# TSOC_GROVEY_GPIO.net
KiCad netlist of a schematic drawn in EAGLE
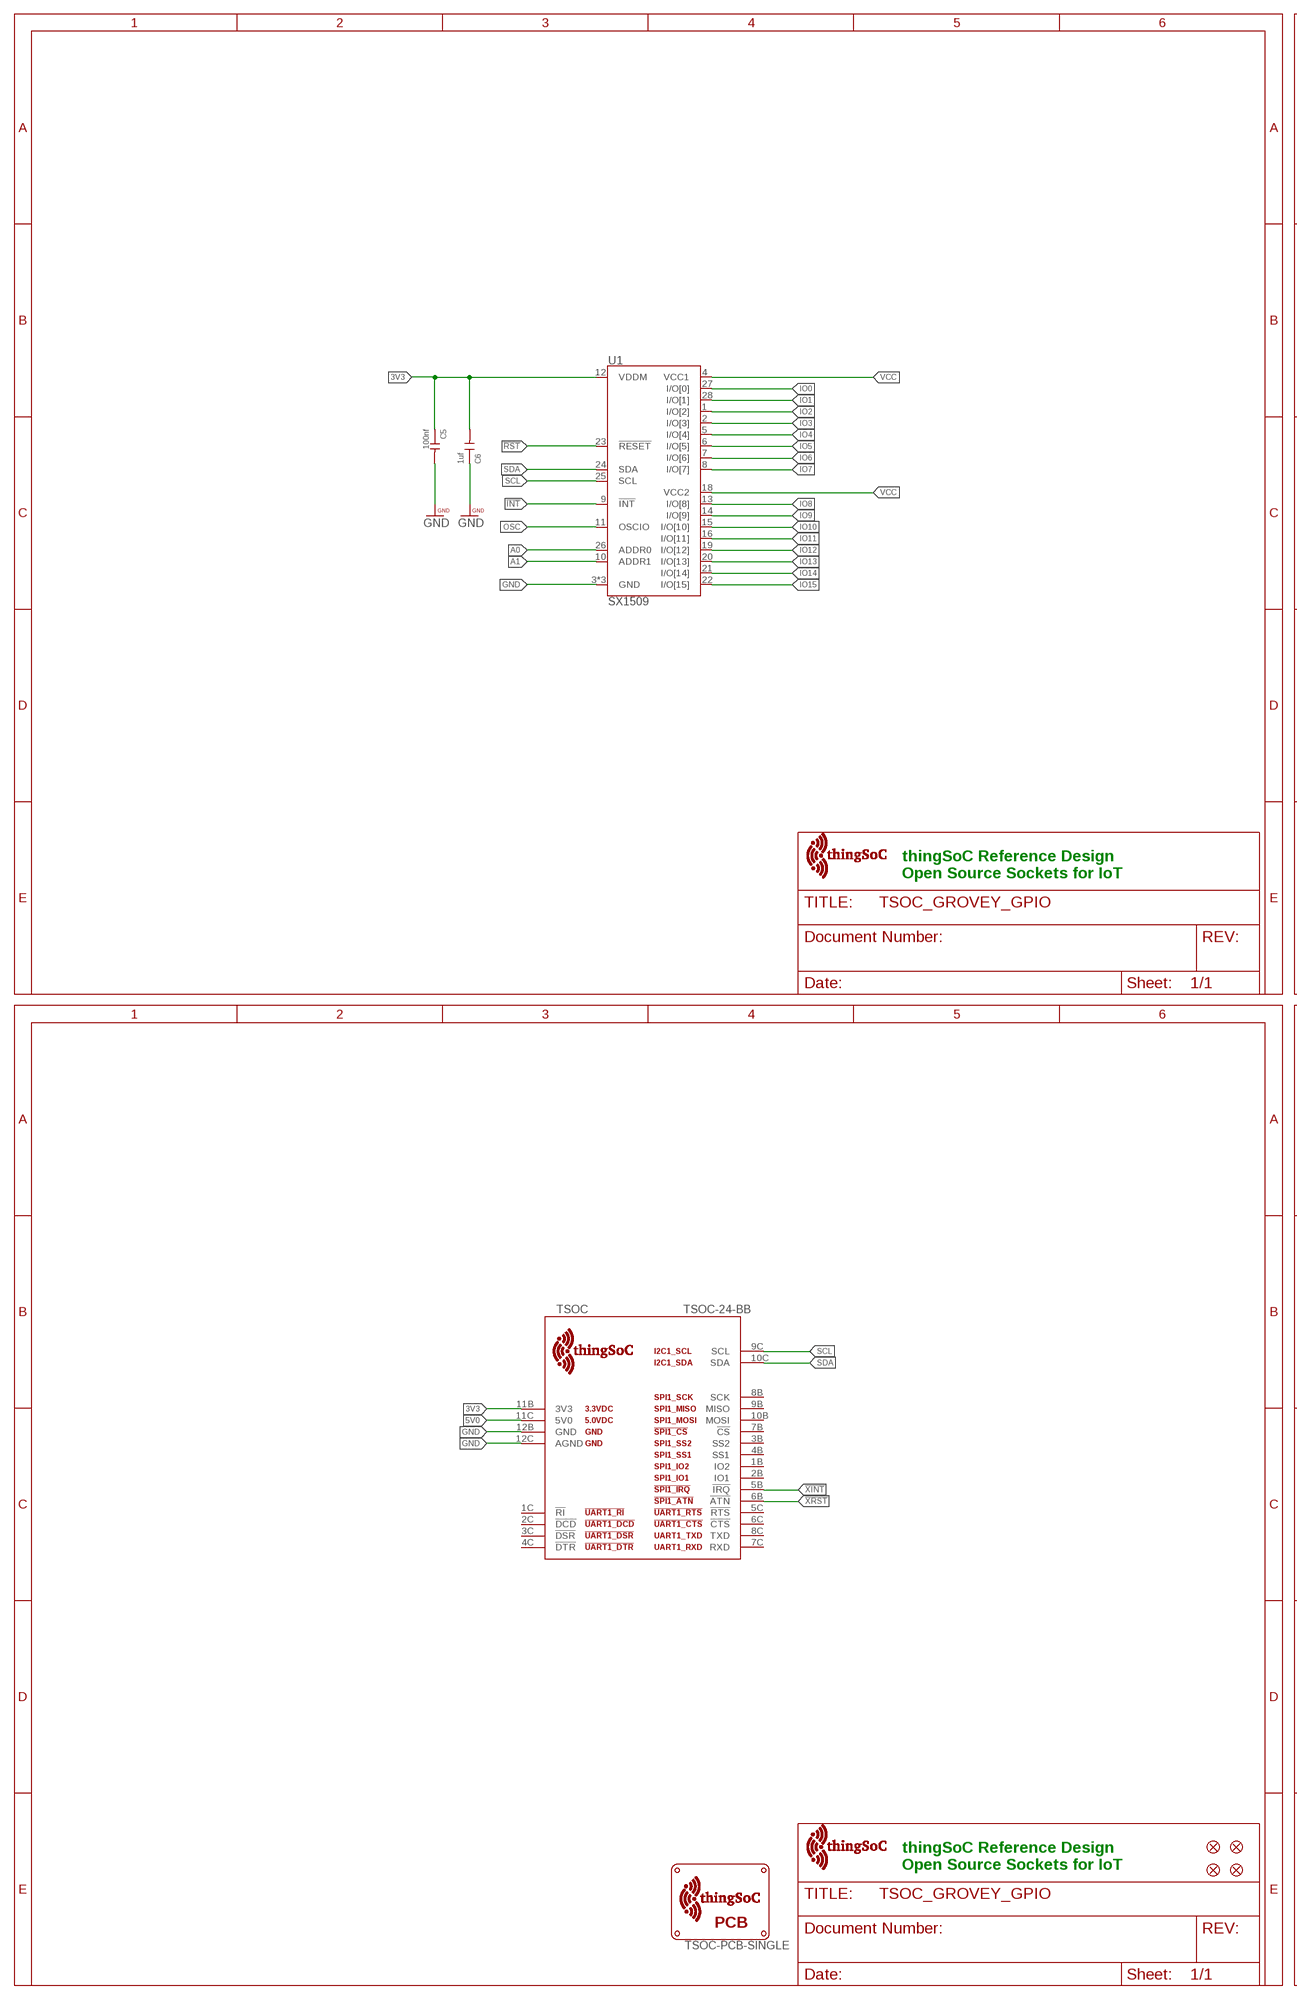
[diagram p0: schematic, sheet 1, part 1 of 2]
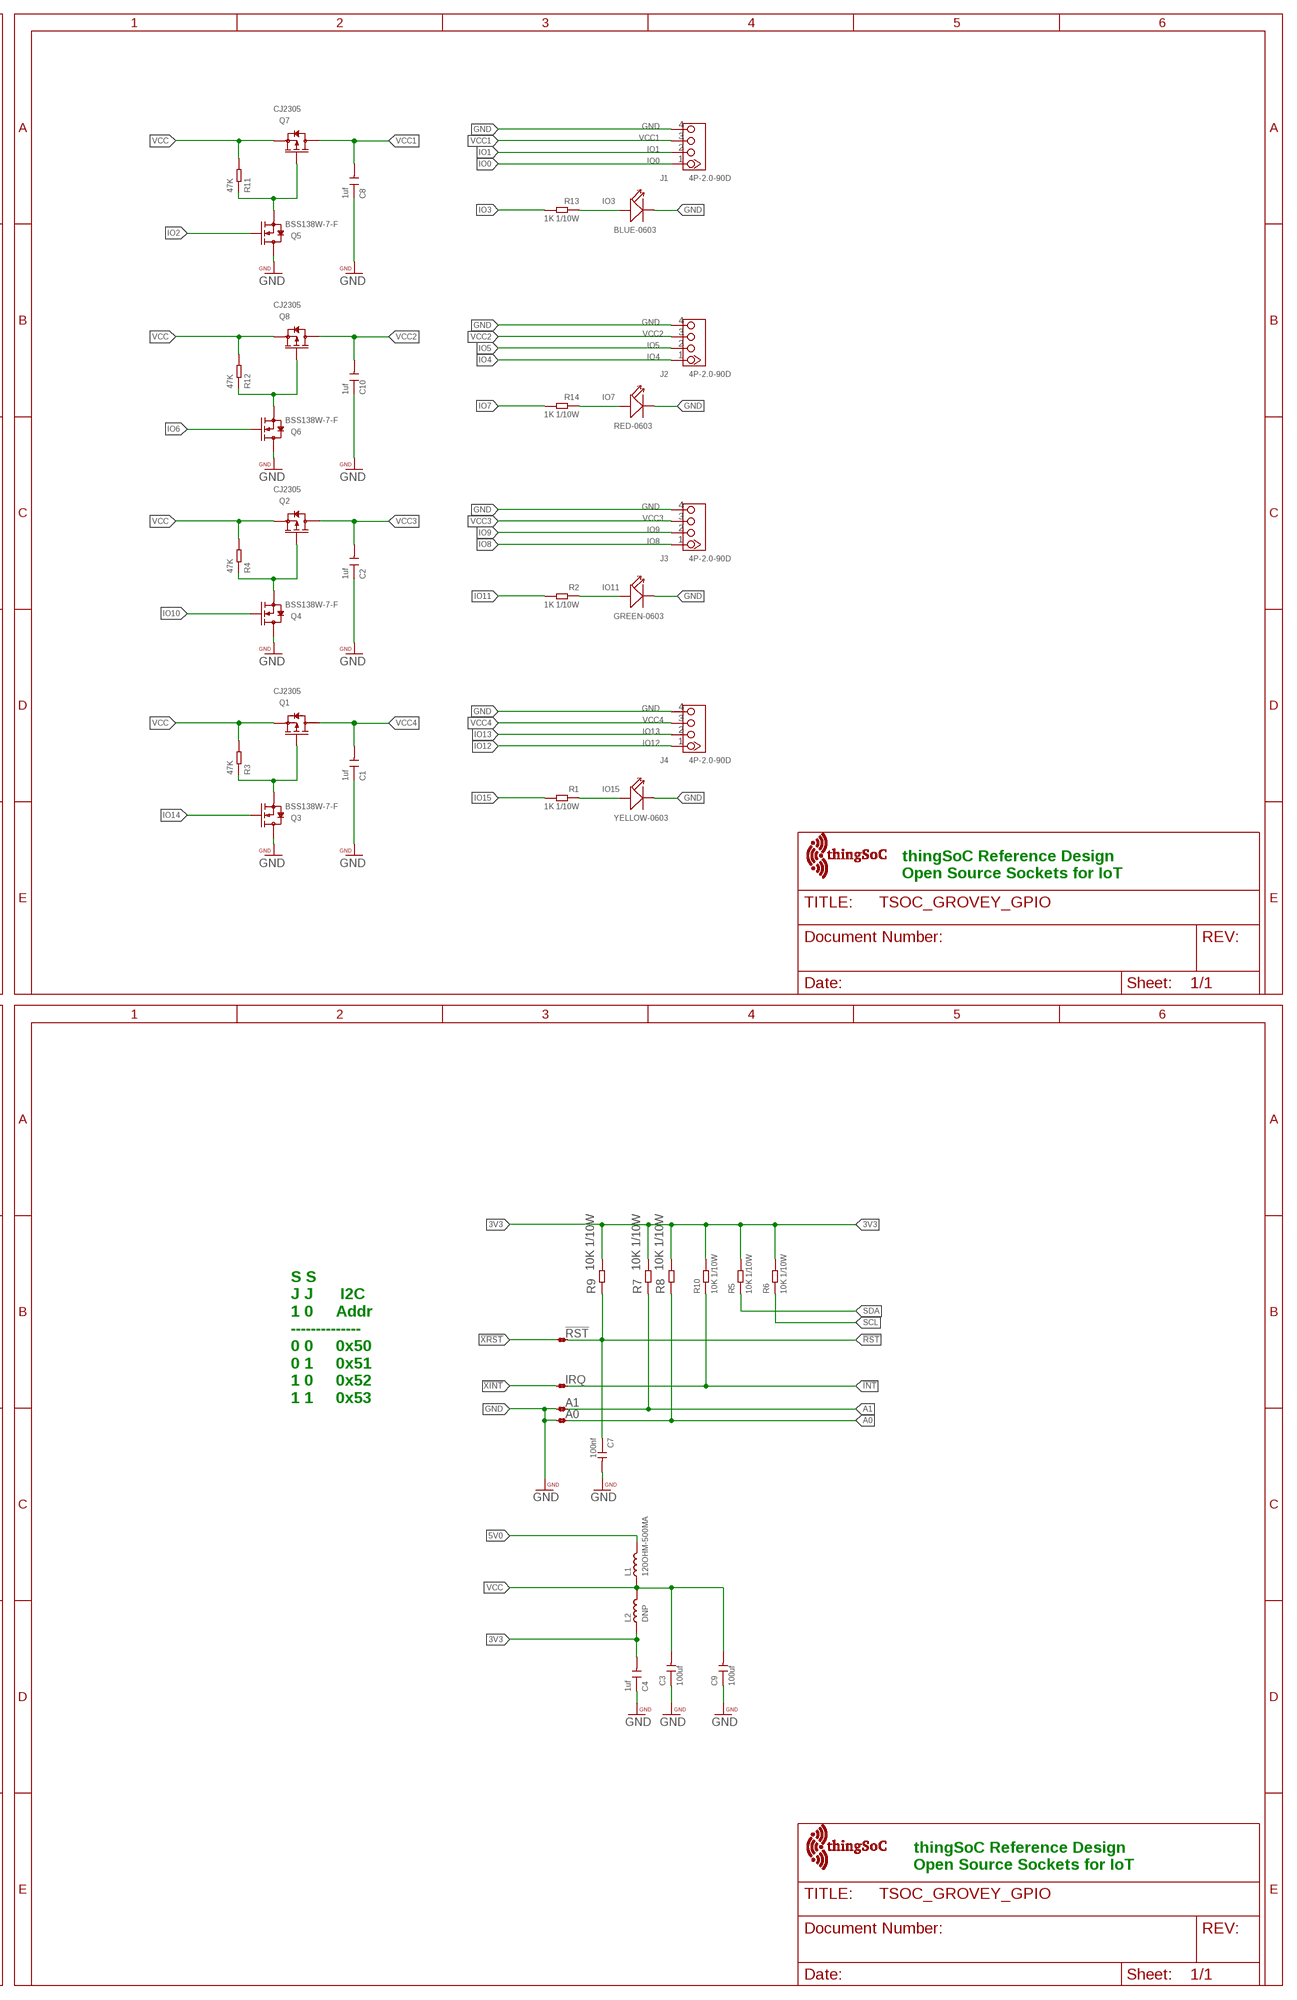
[diagram p1: schematic, sheet 1, part 2 of 2]

(export (version "E")
  (design (tool "Eeschema 10.0.6"))
  (components
    (comp (ref "!RST")
      (value "NO")
      (footprint "eagle-import:JMP-2-NO")
      (libsource (lib "eagle-import") (part "JMP-2-NO"))
    )
    (comp (ref "$$U$4")
      (value "TSOC-LOGO-SMALL")
      (footprint "eagle-import:TSOC-LOGO-SML")
      (libsource (lib "eagle-import") (part "TSOC-LOGO-SMALL"))
    )
    (comp (ref "$$U$5")
      (value "TSOC-LOGO-SMALL")
      (footprint "eagle-import:TSOC-LOGO-SML")
      (libsource (lib "eagle-import") (part "TSOC-LOGO-SMALL"))
    )
    (comp (ref "A0")
      (value "NO")
      (footprint "eagle-import:JMP-2-NO")
      (libsource (lib "eagle-import") (part "JMP-2-NO"))
    )
    (comp (ref "A1")
      (value "NO")
      (footprint "eagle-import:JMP-2-NO")
      (libsource (lib "eagle-import") (part "JMP-2-NO"))
    )
    (comp (ref "C1")
      (value "1uf")
      (footprint "eagle-import:C0603")
      (fields (field (name "MPN") "CC0603KRX7R8BB105"))
      (libsource (lib "eagle-import") (part "CERAMIC-1UF-25V-10%-X7R(0603)"))
    )
    (comp (ref "C2")
      (value "1uf")
      (footprint "eagle-import:C0603")
      (fields (field (name "MPN") "CC0603KRX7R8BB105"))
      (libsource (lib "eagle-import") (part "CERAMIC-1UF-25V-10%-X7R(0603)"))
    )
    (comp (ref "C3")
      (value "100uf")
      (footprint "eagle-import:C1206")
      (fields (field (name "MPN") "GRM31CR60J107ME39L"))
      (libsource (lib "eagle-import") (part "CERAMIC-100UF-6.3V-20%-X5R(1206)"))
    )
    (comp (ref "C4")
      (value "1uf")
      (footprint "eagle-import:C0603")
      (fields (field (name "MPN") "CC0603KRX7R8BB105"))
      (libsource (lib "eagle-import") (part "CERAMIC-1UF-25V-10%-X7R(0603)"))
    )
    (comp (ref "C5")
      (value "100nf")
      (footprint "eagle-import:C0603")
      (fields (field (name "MPN") "CC0603KRX7R9BB104"))
      (libsource (lib "eagle-import") (part "CERAMIC-100NF-50V-10%-X7R(0603)"))
    )
    (comp (ref "C6")
      (value "1uf")
      (footprint "eagle-import:C0603")
      (fields (field (name "MPN") "CC0603KRX7R8BB105"))
      (libsource (lib "eagle-import") (part "CERAMIC-1UF-25V-10%-X7R(0603)"))
    )
    (comp (ref "C7")
      (value "100nf")
      (footprint "eagle-import:C0603")
      (fields (field (name "MPN") "CC0603KRX7R9BB104"))
      (libsource (lib "eagle-import") (part "CERAMIC-100NF-50V-10%-X7R(0603)"))
    )
    (comp (ref "C8")
      (value "1uf")
      (footprint "eagle-import:C0603")
      (fields (field (name "MPN") "CC0603KRX7R8BB105"))
      (libsource (lib "eagle-import") (part "CERAMIC-1UF-25V-10%-X7R(0603)"))
    )
    (comp (ref "C9")
      (value "100uf")
      (footprint "eagle-import:C1206")
      (fields (field (name "MPN") "GRM31CR60J107ME39L"))
      (libsource (lib "eagle-import") (part "CERAMIC-100UF-6.3V-20%-X5R(1206)"))
    )
    (comp (ref "C10")
      (value "1uf")
      (footprint "eagle-import:C0603")
      (fields (field (name "MPN") "CC0603KRX7R8BB105"))
      (libsource (lib "eagle-import") (part "CERAMIC-1UF-25V-10%-X7R(0603)"))
    )
    (comp (ref "FID1")
      (value "FIDUCIALUFIDUCIAL")
      (footprint "eagle-import:MICRO-FIDUCIAL")
      (libsource (lib "eagle-import") (part "FIDUCIALUFIDUCIAL"))
    )
    (comp (ref "FID2")
      (value "FIDUCIALUFIDUCIAL")
      (footprint "eagle-import:MICRO-FIDUCIAL")
      (libsource (lib "eagle-import") (part "FIDUCIALUFIDUCIAL"))
    )
    (comp (ref "FID3")
      (value "FIDUCIALUFIDUCIAL")
      (footprint "eagle-import:MICRO-FIDUCIAL")
      (libsource (lib "eagle-import") (part "FIDUCIALUFIDUCIAL"))
    )
    (comp (ref "FID4")
      (value "FIDUCIALUFIDUCIAL")
      (footprint "eagle-import:MICRO-FIDUCIAL")
      (libsource (lib "eagle-import") (part "FIDUCIALUFIDUCIAL"))
    )
    (comp (ref "IO3")
      (value "BLUE-0603")
      (footprint "eagle-import:LED-0603")
      (fields (field (name "MPN") "19-217-BHC-ZL1M2RY-3T"))
      (libsource (lib "eagle-import") (part "SMD-LED-CLEAR-BLUE(0603)"))
    )
    (comp (ref "IO7")
      (value "RED-0603")
      (footprint "eagle-import:LED-0603")
      (fields (field (name "MPN") "19-217-R6C-AL1M2VY-3T"))
      (libsource (lib "eagle-import") (part "LED-SMD-RED-DIFFUSED(0603)"))
    )
    (comp (ref "IO11")
      (value "GREEN-0603")
      (footprint "eagle-import:LED-0603")
      (fields (field (name "MPN") "19-217-G7C-AN1P2-3T"))
      (libsource (lib "eagle-import") (part "SMD-LED-CLEAR-GREEN(0603)"))
    )
    (comp (ref "IO15")
      (value "YELLOW-0603")
      (footprint "eagle-import:LED-0603")
      (fields (field (name "MPN") "19-217-Y5C-AM1N1VY-3T"))
      (libsource (lib "eagle-import") (part "SMD-LED-CLEAR-YELLOW(0603)"))
    )
    (comp (ref "IRQ")
      (value "NO")
      (footprint "eagle-import:JMP-2-NO")
      (libsource (lib "eagle-import") (part "JMP-2-NO"))
    )
    (comp (ref "J1")
      (value "4P-2.0-90D")
      (footprint "eagle-import:HW4-2.0-90D")
      (libsource (lib "eagle-import") (part "GROVE-CONNECTOR-DIP-90D(4P-2.0)"))
    )
    (comp (ref "J2")
      (value "4P-2.0-90D")
      (footprint "eagle-import:HW4-2.0-90D")
      (libsource (lib "eagle-import") (part "GROVE-CONNECTOR-DIP-90D(4P-2.0)"))
    )
    (comp (ref "J3")
      (value "4P-2.0-90D")
      (footprint "eagle-import:HW4-2.0-90D")
      (libsource (lib "eagle-import") (part "GROVE-CONNECTOR-DIP-90D(4P-2.0)"))
    )
    (comp (ref "J4")
      (value "4P-2.0-90D")
      (footprint "eagle-import:HW4-2.0-90D")
      (libsource (lib "eagle-import") (part "GROVE-CONNECTOR-DIP-90D(4P-2.0)"))
    )
    (comp (ref "L1")
      (value "120OHM-500MA")
      (footprint "eagle-import:L0603")
      (fields (field (name "MPN") "BLM18AG121SN1D"))
      (libsource (lib "eagle-import") (part "SMD-FERRITE-CHIP-120-OHM-500MA(0603)"))
    )
    (comp (ref "L2")
      (value "DNP")
      (footprint "eagle-import:L0603")
      (fields (field (name "MPN") "BLM18AG121SN1D"))
      (libsource (lib "eagle-import") (part "SMD-FERRITE-CHIP-120-OHM-500MA(0603)"))
    )
    (comp (ref "Q1")
      (value "CJ2305")
      (footprint "eagle-import:SOT-23")
      (libsource (lib "eagle-import") (part "SMD-MOSFET-P-CH-8V-4.1A-CJ2305(SOT-23)"))
    )
    (comp (ref "Q2")
      (value "CJ2305")
      (footprint "eagle-import:SOT-23")
      (libsource (lib "eagle-import") (part "SMD-MOSFET-P-CH-8V-4.1A-CJ2305(SOT-23)"))
    )
    (comp (ref "Q3")
      (value "BSS138W-7-F")
      (footprint "eagle-import:SOT-23")
      (libsource (lib "eagle-import") (part "SMD-MOSFET-N-CH-50V-200MA-BSS138W-7-F(SOT-23)"))
    )
    (comp (ref "Q4")
      (value "BSS138W-7-F")
      (footprint "eagle-import:SOT-23")
      (libsource (lib "eagle-import") (part "SMD-MOSFET-N-CH-50V-200MA-BSS138W-7-F(SOT-23)"))
    )
    (comp (ref "Q5")
      (value "BSS138W-7-F")
      (footprint "eagle-import:SOT-23")
      (libsource (lib "eagle-import") (part "SMD-MOSFET-N-CH-50V-200MA-BSS138W-7-F(SOT-23)"))
    )
    (comp (ref "Q6")
      (value "BSS138W-7-F")
      (footprint "eagle-import:SOT-23")
      (libsource (lib "eagle-import") (part "SMD-MOSFET-N-CH-50V-200MA-BSS138W-7-F(SOT-23)"))
    )
    (comp (ref "Q7")
      (value "CJ2305")
      (footprint "eagle-import:SOT-23")
      (libsource (lib "eagle-import") (part "SMD-MOSFET-P-CH-8V-4.1A-CJ2305(SOT-23)"))
    )
    (comp (ref "Q8")
      (value "CJ2305")
      (footprint "eagle-import:SOT-23")
      (libsource (lib "eagle-import") (part "SMD-MOSFET-P-CH-8V-4.1A-CJ2305(SOT-23)"))
    )
    (comp (ref "R1")
      (value "1K 1/10W")
      (footprint "eagle-import:R0603")
      (fields (field (name "MPN") "RC0603JR-071KL"))
      (libsource (lib "eagle-import") (part "SMD-RES-1K-5%-1/10W(0603)"))
    )
    (comp (ref "R2")
      (value "1K 1/10W")
      (footprint "eagle-import:R0603")
      (fields (field (name "MPN") "RC0603JR-071KL"))
      (libsource (lib "eagle-import") (part "SMD-RES-1K-5%-1/10W(0603)"))
    )
    (comp (ref "R3")
      (value "47K")
      (footprint "eagle-import:R0603")
      (fields (field (name "MPN") "RC0603JR-0747KL"))
      (libsource (lib "eagle-import") (part "SMD-RES-47K-5%-1/10W(0603)"))
    )
    (comp (ref "R4")
      (value "47K")
      (footprint "eagle-import:R0603")
      (fields (field (name "MPN") "RC0603JR-0747KL"))
      (libsource (lib "eagle-import") (part "SMD-RES-47K-5%-1/10W(0603)"))
    )
    (comp (ref "R5")
      (value "10K 1/10W")
      (footprint "eagle-import:R0603")
      (fields (field (name "MPN") "RC0603JR-0710KL"))
      (libsource (lib "eagle-import") (part "SMD-RES-10K-5%-1/10W(0603)"))
    )
    (comp (ref "R6")
      (value "10K 1/10W")
      (footprint "eagle-import:R0603")
      (fields (field (name "MPN") "RC0603JR-0710KL"))
      (libsource (lib "eagle-import") (part "SMD-RES-10K-5%-1/10W(0603)"))
    )
    (comp (ref "R7")
      (value "10K 1/10W")
      (footprint "eagle-import:R0603")
      (fields (field (name "MPN") "RC0603JR-0710KL"))
      (libsource (lib "eagle-import") (part "SMD-RES-10K-5%-1/10W(0603)"))
    )
    (comp (ref "R8")
      (value "10K 1/10W")
      (footprint "eagle-import:R0603")
      (fields (field (name "MPN") "RC0603JR-0710KL"))
      (libsource (lib "eagle-import") (part "SMD-RES-10K-5%-1/10W(0603)"))
    )
    (comp (ref "R9")
      (value "10K 1/10W")
      (footprint "eagle-import:R0603")
      (fields (field (name "MPN") "RC0603JR-0710KL"))
      (libsource (lib "eagle-import") (part "SMD-RES-10K-5%-1/10W(0603)"))
    )
    (comp (ref "R10")
      (value "10K 1/10W")
      (footprint "eagle-import:R0603")
      (fields (field (name "MPN") "RC0603JR-0710KL"))
      (libsource (lib "eagle-import") (part "SMD-RES-10K-5%-1/10W(0603)"))
    )
    (comp (ref "R11")
      (value "47K")
      (footprint "eagle-import:R0603")
      (fields (field (name "MPN") "RC0603JR-0747KL"))
      (libsource (lib "eagle-import") (part "SMD-RES-47K-5%-1/10W(0603)"))
    )
    (comp (ref "R12")
      (value "47K")
      (footprint "eagle-import:R0603")
      (fields (field (name "MPN") "RC0603JR-0747KL"))
      (libsource (lib "eagle-import") (part "SMD-RES-47K-5%-1/10W(0603)"))
    )
    (comp (ref "R13")
      (value "1K 1/10W")
      (footprint "eagle-import:R0603")
      (fields (field (name "MPN") "RC0603JR-071KL"))
      (libsource (lib "eagle-import") (part "SMD-RES-1K-5%-1/10W(0603)"))
    )
    (comp (ref "R14")
      (value "1K 1/10W")
      (footprint "eagle-import:R0603")
      (fields (field (name "MPN") "RC0603JR-071KL"))
      (libsource (lib "eagle-import") (part "SMD-RES-1K-5%-1/10W(0603)"))
    )
    (comp (ref "TSOC")
      (value "TSOC-24-BB")
      (footprint "eagle-import:TSOC-BB-S24")
      (libsource (lib "eagle-import") (part "TSOC-24-BB"))
    )
    (comp (ref "U$3")
      (value "TSOC-PCB-SINGLE")
      (footprint "eagle-import:TSOC-BB-BRD-DIM")
      (libsource (lib "eagle-import") (part "TSOC-PCB-SINGLE"))
    )
    (comp (ref "U$101")
      (value "TSOC-LOGO-LRG")
      (footprint "eagle-import:TSOC-LOGO-LRG")
      (libsource (lib "eagle-import") (part "TSOC-LOGO-LRG"))
    )
    (comp (ref "U$102")
      (value "TSOC-LOGO-SMALL")
      (footprint "eagle-import:TSOC-LOGO-SML")
      (libsource (lib "eagle-import") (part "TSOC-LOGO-SMALL"))
    )
    (comp (ref "U1")
      (value "SX1509")
      (footprint "eagle-import:QFN-28")
      (libsource (lib "eagle-import") (part "SX1509"))
    )
  )
  (nets
    (net (code "1") (name "/~{INT}") (class "Default")
      (node (ref "IRQ") (pin "2") (pinfunction "2_2") (pintype "passive"))
      (node (ref "R10") (pin "1") (pinfunction "1_1") (pintype "passive"))
      (node (ref "U1") (pin "9") (pinfunction "~{INT}_9") (pintype "bidirectional"))
    )
    (net (code "2") (name "/~{RST}") (class "Default")
      (node (ref "!RST") (pin "1") (pinfunction "1_1") (pintype "passive"))
      (node (ref "C7") (pin "1") (pinfunction "1_1") (pintype "passive"))
      (node (ref "R9") (pin "1") (pinfunction "1_1") (pintype "passive"))
      (node (ref "U1") (pin "23") (pinfunction "~{RESET}_23") (pintype "bidirectional"))
    )
    (net (code "3") (name "/~{XINT}") (class "Default")
      (node (ref "IRQ") (pin "1") (pinfunction "1_1") (pintype "passive"))
      (node (ref "TSOC") (pin "5B") (pinfunction "~{IRQ}_5B") (pintype "bidirectional"))
    )
    (net (code "4") (name "/~{XRST}") (class "Default")
      (node (ref "!RST") (pin "2") (pinfunction "2_2") (pintype "passive"))
      (node (ref "TSOC") (pin "6B") (pinfunction "~{ATN}_6B") (pintype "bidirectional"))
    )
    (net (code "5") (name "3V3") (class "Default")
      (node (ref "C4") (pin "2") (pinfunction "2_2") (pintype "passive"))
      (node (ref "C5") (pin "1") (pinfunction "1_1") (pintype "passive"))
      (node (ref "C6") (pin "2") (pinfunction "2_2") (pintype "passive"))
      (node (ref "L2") (pin "1") (pinfunction "1_1") (pintype "passive"))
      (node (ref "R10") (pin "2") (pinfunction "2_2") (pintype "passive"))
      (node (ref "R5") (pin "2") (pinfunction "2_2") (pintype "passive"))
      (node (ref "R6") (pin "2") (pinfunction "2_2") (pintype "passive"))
      (node (ref "R7") (pin "2") (pinfunction "2_2") (pintype "passive"))
      (node (ref "R8") (pin "2") (pinfunction "2_2") (pintype "passive"))
      (node (ref "R9") (pin "2") (pinfunction "2_2") (pintype "passive"))
      (node (ref "TSOC") (pin "11B") (pinfunction "3V3_11B") (pintype "bidirectional"))
      (node (ref "U1") (pin "12") (pinfunction "VDDM_12") (pintype "bidirectional"))
    )
    (net (code "6") (name "5V0") (class "Default")
      (node (ref "L1") (pin "2") (pinfunction "2_2") (pintype "passive"))
      (node (ref "TSOC") (pin "11C") (pinfunction "5V0_11C") (pintype "bidirectional"))
    )
    (net (code "7") (name "A0") (class "Default")
      (node (ref "A0") (pin "2") (pinfunction "2_2") (pintype "passive"))
      (node (ref "R8") (pin "1") (pinfunction "1_1") (pintype "passive"))
      (node (ref "U1") (pin "26") (pinfunction "ADDR0_26") (pintype "bidirectional"))
    )
    (net (code "8") (name "A1") (class "Default")
      (node (ref "A1") (pin "2") (pinfunction "2_2") (pintype "passive"))
      (node (ref "R7") (pin "1") (pinfunction "1_1") (pintype "passive"))
      (node (ref "U1") (pin "10") (pinfunction "ADDR1_10") (pintype "bidirectional"))
    )
    (net (code "9") (name "GND") (class "Default")
      (node (ref "A0") (pin "1") (pinfunction "1_1") (pintype "passive"))
      (node (ref "A1") (pin "1") (pinfunction "1_1") (pintype "passive"))
      (node (ref "C1") (pin "1") (pinfunction "1_1") (pintype "passive"))
      (node (ref "C10") (pin "1") (pinfunction "1_1") (pintype "passive"))
      (node (ref "C2") (pin "1") (pinfunction "1_1") (pintype "passive"))
      (node (ref "C3") (pin "1") (pinfunction "1_1") (pintype "passive"))
      (node (ref "C4") (pin "1") (pinfunction "1_1") (pintype "passive"))
      (node (ref "C5") (pin "2") (pinfunction "2_2") (pintype "passive"))
      (node (ref "C6") (pin "1") (pinfunction "1_1") (pintype "passive"))
      (node (ref "C7") (pin "2") (pinfunction "2_2") (pintype "passive"))
      (node (ref "C8") (pin "1") (pinfunction "1_1") (pintype "passive"))
      (node (ref "C9") (pin "1") (pinfunction "1_1") (pintype "passive"))
      (node (ref "IO11") (pin "-") (pinfunction "-_-") (pintype "passive"))
      (node (ref "IO15") (pin "-") (pinfunction "-_-") (pintype "passive"))
      (node (ref "IO3") (pin "-") (pinfunction "-_-") (pintype "passive"))
      (node (ref "IO7") (pin "-") (pinfunction "-_-") (pintype "passive"))
      (node (ref "J1") (pin "4") (pinfunction "4_4") (pintype "bidirectional"))
      (node (ref "J2") (pin "4") (pinfunction "4_4") (pintype "bidirectional"))
      (node (ref "J3") (pin "4") (pinfunction "4_4") (pintype "bidirectional"))
      (node (ref "J4") (pin "4") (pinfunction "4_4") (pintype "bidirectional"))
      (node (ref "Q3") (pin "3") (pinfunction "D_3") (pintype "passive"))
      (node (ref "Q4") (pin "3") (pinfunction "D_3") (pintype "passive"))
      (node (ref "Q5") (pin "3") (pinfunction "D_3") (pintype "passive"))
      (node (ref "Q6") (pin "3") (pinfunction "D_3") (pintype "passive"))
      (node (ref "TSOC") (pin "12B") (pinfunction "GND_12B") (pintype "bidirectional"))
      (node (ref "TSOC") (pin "12C") (pinfunction "AGND_12C") (pintype "bidirectional"))
      (node (ref "U1") (pin "17") (pinfunction "GND_17") (pintype "bidirectional"))
      (node (ref "U1") (pin "29") (pinfunction "GND_29") (pintype "bidirectional"))
      (node (ref "U1") (pin "3") (pinfunction "GND_3") (pintype "bidirectional"))
    )
    (net (code "10") (name "IO0") (class "Default")
      (node (ref "J1") (pin "1") (pinfunction "1_1") (pintype "bidirectional"))
      (node (ref "U1") (pin "27") (pinfunction "I/O[0]_27") (pintype "bidirectional"))
    )
    (net (code "11") (name "IO1") (class "Default")
      (node (ref "J1") (pin "2") (pinfunction "2_2") (pintype "bidirectional"))
      (node (ref "U1") (pin "28") (pinfunction "I/O[1]_28") (pintype "bidirectional"))
    )
    (net (code "12") (name "IO2") (class "Default")
      (node (ref "Q5") (pin "1") (pinfunction "G_1") (pintype "passive"))
      (node (ref "U1") (pin "1") (pinfunction "I/O[2]_1") (pintype "bidirectional"))
    )
    (net (code "13") (name "IO3") (class "Default")
      (node (ref "R13") (pin "2") (pinfunction "2_2") (pintype "passive"))
      (node (ref "U1") (pin "2") (pinfunction "I/O[3]_2") (pintype "bidirectional"))
    )
    (net (code "14") (name "IO4") (class "Default")
      (node (ref "J2") (pin "1") (pinfunction "1_1") (pintype "bidirectional"))
      (node (ref "U1") (pin "5") (pinfunction "I/O[4]_5") (pintype "bidirectional"))
    )
    (net (code "15") (name "IO5") (class "Default")
      (node (ref "J2") (pin "2") (pinfunction "2_2") (pintype "bidirectional"))
      (node (ref "U1") (pin "6") (pinfunction "I/O[5]_6") (pintype "bidirectional"))
    )
    (net (code "16") (name "IO6") (class "Default")
      (node (ref "Q6") (pin "1") (pinfunction "G_1") (pintype "passive"))
      (node (ref "U1") (pin "7") (pinfunction "I/O[6]_7") (pintype "bidirectional"))
    )
    (net (code "17") (name "IO7") (class "Default")
      (node (ref "R14") (pin "2") (pinfunction "2_2") (pintype "passive"))
      (node (ref "U1") (pin "8") (pinfunction "I/O[7]_8") (pintype "bidirectional"))
    )
    (net (code "18") (name "IO8") (class "Default")
      (node (ref "J3") (pin "1") (pinfunction "1_1") (pintype "bidirectional"))
      (node (ref "U1") (pin "13") (pinfunction "I/O[8]_13") (pintype "bidirectional"))
    )
    (net (code "19") (name "IO9") (class "Default")
      (node (ref "J3") (pin "2") (pinfunction "2_2") (pintype "bidirectional"))
      (node (ref "U1") (pin "14") (pinfunction "I/O[9]_14") (pintype "bidirectional"))
    )
    (net (code "20") (name "IO10") (class "Default")
      (node (ref "Q4") (pin "1") (pinfunction "G_1") (pintype "passive"))
      (node (ref "U1") (pin "15") (pinfunction "I/O[10]_15") (pintype "bidirectional"))
    )
    (net (code "21") (name "IO11") (class "Default")
      (node (ref "R2") (pin "2") (pinfunction "2_2") (pintype "passive"))
      (node (ref "U1") (pin "16") (pinfunction "I/O[11]_16") (pintype "bidirectional"))
    )
    (net (code "22") (name "IO12") (class "Default")
      (node (ref "J4") (pin "1") (pinfunction "1_1") (pintype "bidirectional"))
      (node (ref "U1") (pin "19") (pinfunction "I/O[12]_19") (pintype "bidirectional"))
    )
    (net (code "23") (name "IO13") (class "Default")
      (node (ref "J4") (pin "2") (pinfunction "2_2") (pintype "bidirectional"))
      (node (ref "U1") (pin "20") (pinfunction "I/O[13]_20") (pintype "bidirectional"))
    )
    (net (code "24") (name "IO14") (class "Default")
      (node (ref "Q3") (pin "1") (pinfunction "G_1") (pintype "passive"))
      (node (ref "U1") (pin "21") (pinfunction "I/O[14]_21") (pintype "bidirectional"))
    )
    (net (code "25") (name "IO15") (class "Default")
      (node (ref "R1") (pin "2") (pinfunction "2_2") (pintype "passive"))
      (node (ref "U1") (pin "22") (pinfunction "I/O[15]_22") (pintype "bidirectional"))
    )
    (net (code "26") (name "Net-(IO3-Pad+)") (class "Default")
      (node (ref "IO3") (pin "+") (pinfunction "+_+") (pintype "passive"))
      (node (ref "R13") (pin "1") (pinfunction "1_1") (pintype "passive"))
    )
    (net (code "27") (name "Net-(IO7-Pad+)") (class "Default")
      (node (ref "IO7") (pin "+") (pinfunction "+_+") (pintype "passive"))
      (node (ref "R14") (pin "1") (pinfunction "1_1") (pintype "passive"))
    )
    (net (code "28") (name "Net-(IO11-Pad+)") (class "Default")
      (node (ref "IO11") (pin "+") (pinfunction "+_+") (pintype "passive"))
      (node (ref "R2") (pin "1") (pinfunction "1_1") (pintype "passive"))
    )
    (net (code "29") (name "Net-(IO15-Pad+)") (class "Default")
      (node (ref "IO15") (pin "+") (pinfunction "+_+") (pintype "passive"))
      (node (ref "R1") (pin "1") (pinfunction "1_1") (pintype "passive"))
    )
    (net (code "30") (name "Net-(Q1-G)") (class "Default")
      (node (ref "Q1") (pin "1") (pinfunction "G_1") (pintype "passive"))
      (node (ref "Q3") (pin "2") (pinfunction "S_2") (pintype "passive"))
      (node (ref "R3") (pin "1") (pinfunction "1_1") (pintype "passive"))
    )
    (net (code "31") (name "Net-(Q2-G)") (class "Default")
      (node (ref "Q2") (pin "1") (pinfunction "G_1") (pintype "passive"))
      (node (ref "Q4") (pin "2") (pinfunction "S_2") (pintype "passive"))
      (node (ref "R4") (pin "1") (pinfunction "1_1") (pintype "passive"))
    )
    (net (code "32") (name "Net-(Q5-S)") (class "Default")
      (node (ref "Q5") (pin "2") (pinfunction "S_2") (pintype "passive"))
      (node (ref "Q7") (pin "1") (pinfunction "G_1") (pintype "passive"))
      (node (ref "R11") (pin "1") (pinfunction "1_1") (pintype "passive"))
    )
    (net (code "33") (name "Net-(Q6-S)") (class "Default")
      (node (ref "Q6") (pin "2") (pinfunction "S_2") (pintype "passive"))
      (node (ref "Q8") (pin "1") (pinfunction "G_1") (pintype "passive"))
      (node (ref "R12") (pin "1") (pinfunction "1_1") (pintype "passive"))
    )
    (net (code "34") (name "OSC") (class "Default")
      (node (ref "U1") (pin "11") (pinfunction "OSCIO_11") (pintype "bidirectional"))
    )
    (net (code "35") (name "SCL") (class "Default")
      (node (ref "R6") (pin "1") (pinfunction "1_1") (pintype "passive"))
      (node (ref "TSOC") (pin "9C") (pinfunction "SCL_9C") (pintype "bidirectional"))
      (node (ref "U1") (pin "25") (pinfunction "SCL_25") (pintype "bidirectional"))
    )
    (net (code "36") (name "SDA") (class "Default")
      (node (ref "R5") (pin "1") (pinfunction "1_1") (pintype "passive"))
      (node (ref "TSOC") (pin "10C") (pinfunction "SDA_10C") (pintype "bidirectional"))
      (node (ref "U1") (pin "24") (pinfunction "SDA_24") (pintype "bidirectional"))
    )
    (net (code "37") (name "VCC") (class "Default")
      (node (ref "C3") (pin "2") (pinfunction "2_2") (pintype "passive"))
      (node (ref "C9") (pin "2") (pinfunction "2_2") (pintype "passive"))
      (node (ref "L1") (pin "1") (pinfunction "1_1") (pintype "passive"))
      (node (ref "L2") (pin "2") (pinfunction "2_2") (pintype "passive"))
      (node (ref "Q1") (pin "2") (pinfunction "S_2") (pintype "passive"))
      (node (ref "Q2") (pin "2") (pinfunction "S_2") (pintype "passive"))
      (node (ref "Q7") (pin "2") (pinfunction "S_2") (pintype "passive"))
      (node (ref "Q8") (pin "2") (pinfunction "S_2") (pintype "passive"))
      (node (ref "R11") (pin "2") (pinfunction "2_2") (pintype "passive"))
      (node (ref "R12") (pin "2") (pinfunction "2_2") (pintype "passive"))
      (node (ref "R3") (pin "2") (pinfunction "2_2") (pintype "passive"))
      (node (ref "R4") (pin "2") (pinfunction "2_2") (pintype "passive"))
      (node (ref "U1") (pin "18") (pinfunction "VCC2_18") (pintype "bidirectional"))
      (node (ref "U1") (pin "4") (pinfunction "VCC1_4") (pintype "bidirectional"))
    )
    (net (code "38") (name "VCC1") (class "Default")
      (node (ref "C8") (pin "2") (pinfunction "2_2") (pintype "passive"))
      (node (ref "J1") (pin "3") (pinfunction "3_3") (pintype "bidirectional"))
      (node (ref "Q7") (pin "3") (pinfunction "D_3") (pintype "passive"))
    )
    (net (code "39") (name "VCC2") (class "Default")
      (node (ref "C10") (pin "2") (pinfunction "2_2") (pintype "passive"))
      (node (ref "J2") (pin "3") (pinfunction "3_3") (pintype "bidirectional"))
      (node (ref "Q8") (pin "3") (pinfunction "D_3") (pintype "passive"))
    )
    (net (code "40") (name "VCC3") (class "Default")
      (node (ref "C2") (pin "2") (pinfunction "2_2") (pintype "passive"))
      (node (ref "J3") (pin "3") (pinfunction "3_3") (pintype "bidirectional"))
      (node (ref "Q2") (pin "3") (pinfunction "D_3") (pintype "passive"))
    )
    (net (code "41") (name "VCC4") (class "Default")
      (node (ref "C1") (pin "2") (pinfunction "2_2") (pintype "passive"))
      (node (ref "J4") (pin "3") (pinfunction "3_3") (pintype "bidirectional"))
      (node (ref "Q1") (pin "3") (pinfunction "D_3") (pintype "passive"))
    )
    (net (code "42") (name "unconnected-(TSOC-IO1-Pad2B)") (class "Default")
      (node (ref "TSOC") (pin "2B") (pinfunction "IO1_2B") (pintype "bidirectional"))
    )
    (net (code "43") (name "unconnected-(TSOC-IO2-Pad1B)") (class "Default")
      (node (ref "TSOC") (pin "1B") (pinfunction "IO2_1B") (pintype "bidirectional"))
    )
    (net (code "44") (name "unconnected-(TSOC-MISO-Pad9B)") (class "Default")
      (node (ref "TSOC") (pin "9B") (pinfunction "MISO_9B") (pintype "bidirectional"))
    )
    (net (code "45") (name "unconnected-(TSOC-MOSI-Pad10B)") (class "Default")
      (node (ref "TSOC") (pin "10B") (pinfunction "MOSI_10B") (pintype "bidirectional"))
    )
    (net (code "46") (name "unconnected-(TSOC-RXD-Pad7C)") (class "Default")
      (node (ref "TSOC") (pin "7C") (pinfunction "RXD_7C") (pintype "bidirectional"))
    )
    (net (code "47") (name "unconnected-(TSOC-SCK-Pad8B)") (class "Default")
      (node (ref "TSOC") (pin "8B") (pinfunction "SCK_8B") (pintype "bidirectional"))
    )
    (net (code "48") (name "unconnected-(TSOC-SS1-Pad4B)") (class "Default")
      (node (ref "TSOC") (pin "4B") (pinfunction "SS1_4B") (pintype "bidirectional"))
    )
    (net (code "49") (name "unconnected-(TSOC-SS2-Pad3B)") (class "Default")
      (node (ref "TSOC") (pin "3B") (pinfunction "SS2_3B") (pintype "bidirectional"))
    )
    (net (code "50") (name "unconnected-(TSOC-TXD-Pad8C)") (class "Default")
      (node (ref "TSOC") (pin "8C") (pinfunction "TXD_8C") (pintype "bidirectional"))
    )
    (net (code "51") (name "unconnected-(TSOC-~{CS}-Pad7B)") (class "Default")
      (node (ref "TSOC") (pin "7B") (pinfunction "~{CS}_7B") (pintype "bidirectional"))
    )
    (net (code "52") (name "unconnected-(TSOC-~{CTS}-Pad6C)") (class "Default")
      (node (ref "TSOC") (pin "6C") (pinfunction "~{CTS}_6C") (pintype "bidirectional"))
    )
    (net (code "53") (name "unconnected-(TSOC-~{DCD}-Pad2C)") (class "Default")
      (node (ref "TSOC") (pin "2C") (pinfunction "~{DCD}_2C") (pintype "bidirectional"))
    )
    (net (code "54") (name "unconnected-(TSOC-~{DSR}-Pad3C)") (class "Default")
      (node (ref "TSOC") (pin "3C") (pinfunction "~{DSR}_3C") (pintype "bidirectional"))
    )
    (net (code "55") (name "unconnected-(TSOC-~{DTR}-Pad4C)") (class "Default")
      (node (ref "TSOC") (pin "4C") (pinfunction "~{DTR}_4C") (pintype "bidirectional"))
    )
    (net (code "56") (name "unconnected-(TSOC-~{RI}-Pad1C)") (class "Default")
      (node (ref "TSOC") (pin "1C") (pinfunction "~{RI}_1C") (pintype "bidirectional"))
    )
    (net (code "57") (name "unconnected-(TSOC-~{RTS}-Pad5C)") (class "Default")
      (node (ref "TSOC") (pin "5C") (pinfunction "~{RTS}_5C") (pintype "bidirectional"))
    )
  )
)
